# PrimaryBoard.net
KiCad netlist of a schematic drawn in EAGLE
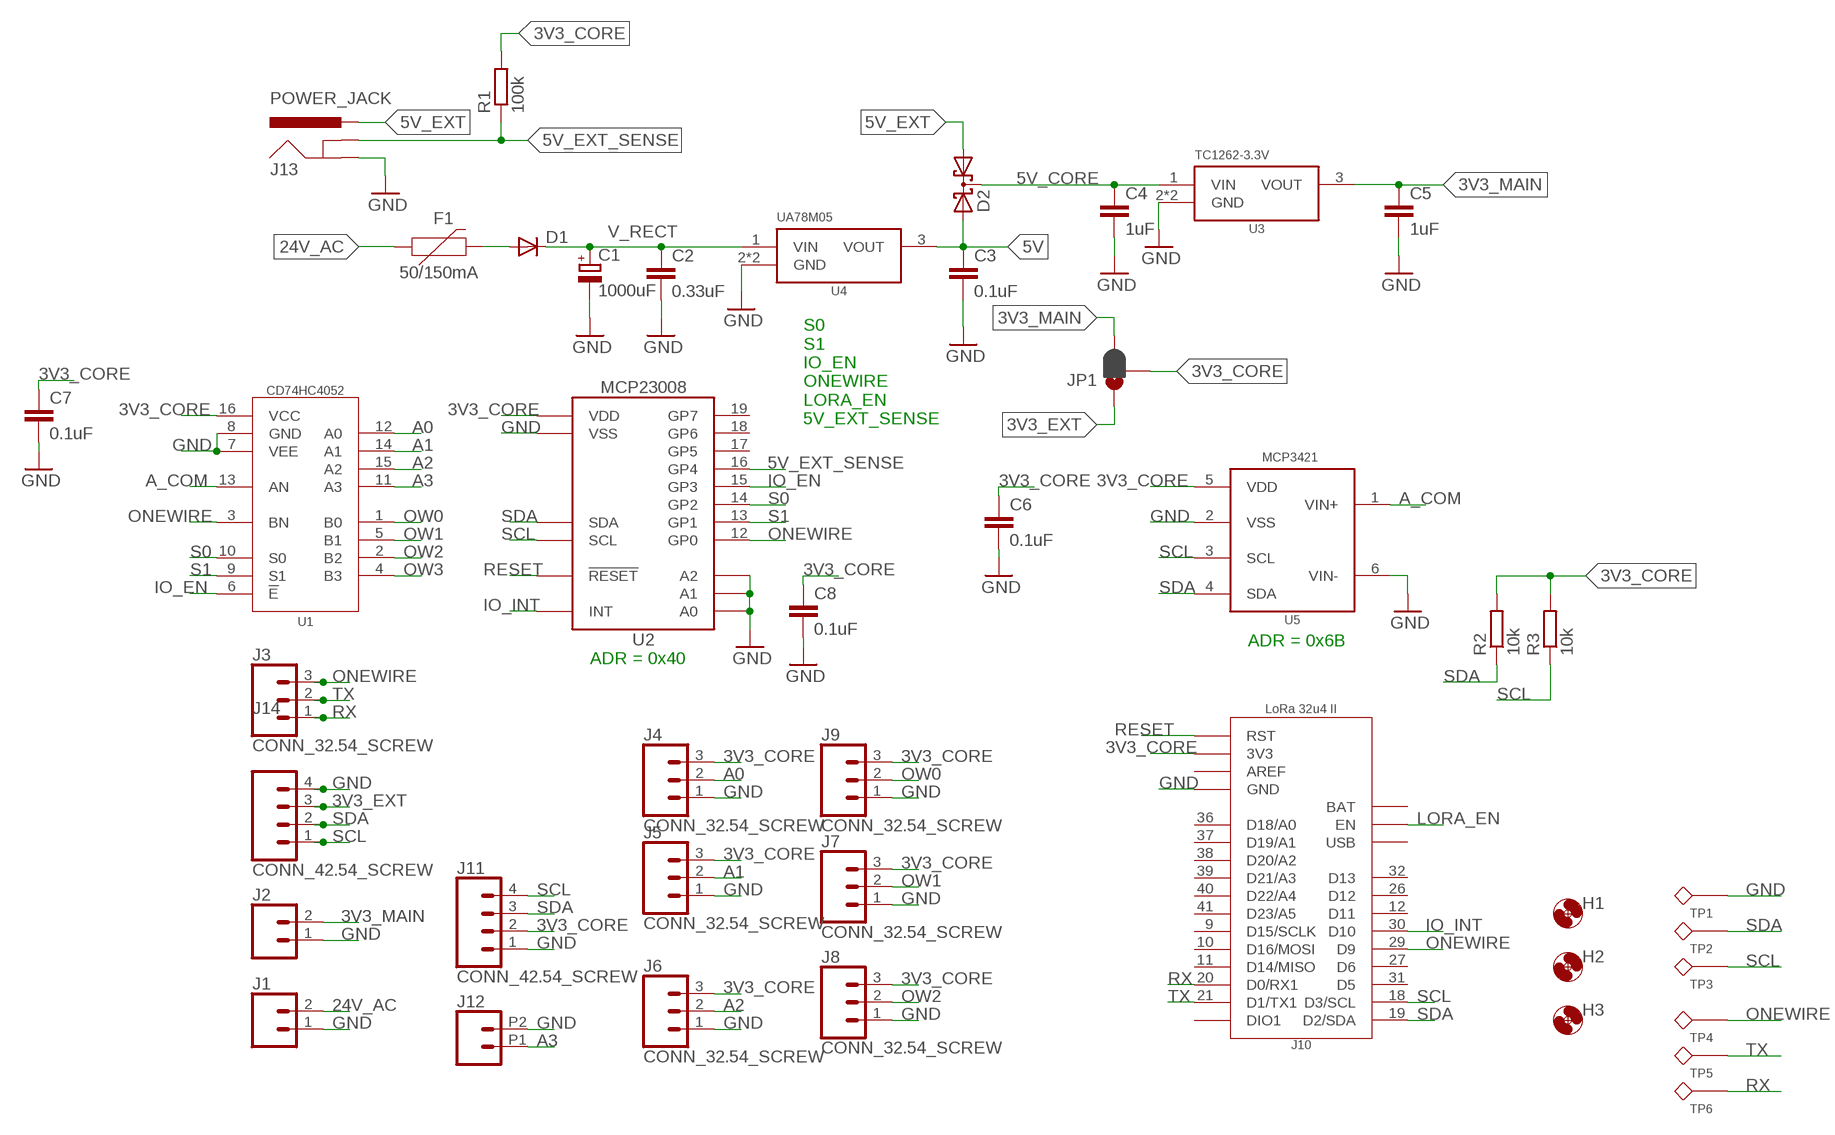
[diagram p0: schematic, sheet 1]

(export (version "E")
  (design (tool "Eeschema 10.0.6"))
  (components
    (comp (ref "C1")
      (value "1000uF")
      (footprint "eagle-import:PANASONIC_G")
      (fields (field (name "MF") "Panasonic") (field (name "MPN") "EEE-FT1E102UP"))
      (libsource (lib "eagle-import") (part "CPOL-EUG"))
    )
    (comp (ref "C2")
      (value "0.33uF")
      (footprint "eagle-import:C0805")
      (fields (field (name "MF") "Yageo") (field (name "MPN") "CC0805KKX7R9BB334"))
      (libsource (lib "eagle-import") (part "C-EUC08050.33UF"))
    )
    (comp (ref "C3")
      (value "0.1uF")
      (footprint "eagle-import:C0805")
      (fields (field (name "MF") "Kemet") (field (name "MPN") "C0805C104M3RACTU"))
      (libsource (lib "eagle-import") (part "C-EUC08050.1UF"))
    )
    (comp (ref "C4")
      (value "1uF")
      (footprint "eagle-import:C0805")
      (fields (field (name "MF") "Yageo") (field (name "MPN") "CC0805KKX7R8BB105"))
      (libsource (lib "eagle-import") (part "C-EUC08051UF"))
    )
    (comp (ref "C5")
      (value "1uF")
      (footprint "eagle-import:C0805")
      (fields (field (name "MF") "Yageo") (field (name "MPN") "CC0805KKX7R8BB105"))
      (libsource (lib "eagle-import") (part "C-EUC08051UF"))
    )
    (comp (ref "C6")
      (value "0.1uF")
      (footprint "eagle-import:C0805")
      (fields (field (name "MF") "Kemet") (field (name "MPN") "C0805C104M3RACTU"))
      (libsource (lib "eagle-import") (part "C-EUC08050.1UF"))
    )
    (comp (ref "C7")
      (value "0.1uF")
      (footprint "eagle-import:C0805")
      (fields (field (name "MF") "Kemet") (field (name "MPN") "C0805C104M3RACTU"))
      (libsource (lib "eagle-import") (part "C-EUC08050.1UF"))
    )
    (comp (ref "C8")
      (value "0.1uF")
      (footprint "eagle-import:C0805")
      (fields (field (name "MF") "Kemet") (field (name "MPN") "C0805C104M3RACTU"))
      (libsource (lib "eagle-import") (part "C-EUC08050.1UF"))
    )
    (comp (ref "D1")
      (value "DIODESOD-123")
      (footprint "eagle-import:SOD-123")
      (fields (field (name "MF") "Diodes Incorporated") (field (name "MPN") "1N5819HW-7-F"))
      (libsource (lib "eagle-import") (part "DIODESOD-123"))
    )
    (comp (ref "D2")
      (value "DIODE_CCSDM40E20LCSOT23")
      (footprint "eagle-import:SOT23-3")
      (fields (field (name "MF") "Diodes Incorporated") (field (name "MPN") "SDM40E20LC-7"))
      (libsource (lib "eagle-import") (part "DIODE_CCSOT23SDM40E20LC"))
    )
    (comp (ref "F1")
      (value "50/150mA")
      (footprint "eagle-import:1206")
      (fields (field (name "MF") "Bell Fuse") (field (name "MPN") "0ZCJ0005FF2E"))
      (libsource (lib "eagle-import") (part "PPTC1206150MA"))
    )
    (comp (ref "H1")
      (value "MOUNTING_HOLE2_NP")
      (footprint "eagle-import:2_56")
      (libsource (lib "eagle-import") (part "MOUNTING_HOLE2_NP"))
    )
    (comp (ref "H2")
      (value "MOUNTING_HOLE2_NP")
      (footprint "eagle-import:2_56")
      (libsource (lib "eagle-import") (part "MOUNTING_HOLE2_NP"))
    )
    (comp (ref "H3")
      (value "MOUNTING_HOLE2_NP")
      (footprint "eagle-import:2_56")
      (libsource (lib "eagle-import") (part "MOUNTING_HOLE2_NP"))
    )
    (comp (ref "J1")
      (value "CONN_0239532_RA")
      (footprint "eagle-import:1X02_39532_RIGHT")
      (fields (field (name "MF") "Molex") (field (name "MPN") "0395321002"))
      (libsource (lib "eagle-import") (part "CONN_0239532_RA"))
    )
    (comp (ref "J2")
      (value "CONN_023.5MM-NO_SILK")
      (footprint "eagle-import:SCREWTERMINAL-3.5MM-2-NS")
      (fields (field (name "MF") "On Shore Technology") (field (name "MPN") "OSTTE020161"))
      (libsource (lib "eagle-import") (part "CONN_023.5MM-NO_SILK"))
    )
    (comp (ref "J3")
      (value "CONN_32.54_SCREW")
      (footprint "eagle-import:1X03_SCREW")
      (fields (field (name "MF") "On Shore") (field (name "MPN") "OSTVN03A150"))
      (libsource (lib "eagle-import") (part "CONN_32.54_SCREW"))
    )
    (comp (ref "J4")
      (value "CONN_32.54_SCREW")
      (footprint "eagle-import:1X03_SCREW")
      (fields (field (name "MF") "On Shore") (field (name "MPN") "OSTVN03A150"))
      (libsource (lib "eagle-import") (part "CONN_32.54_SCREW"))
    )
    (comp (ref "J5")
      (value "CONN_32.54_SCREW")
      (footprint "eagle-import:1X03_SCREW")
      (fields (field (name "MF") "On Shore") (field (name "MPN") "OSTVN03A150"))
      (libsource (lib "eagle-import") (part "CONN_32.54_SCREW"))
    )
    (comp (ref "J6")
      (value "CONN_32.54_SCREW")
      (footprint "eagle-import:1X03_SCREW")
      (fields (field (name "MF") "On Shore") (field (name "MPN") "OSTVN03A150"))
      (libsource (lib "eagle-import") (part "CONN_32.54_SCREW"))
    )
    (comp (ref "J7")
      (value "CONN_32.54_SCREW")
      (footprint "eagle-import:1X03_SCREW")
      (fields (field (name "MF") "On Shore") (field (name "MPN") "OSTVN03A150"))
      (libsource (lib "eagle-import") (part "CONN_32.54_SCREW"))
    )
    (comp (ref "J8")
      (value "CONN_32.54_SCREW")
      (footprint "eagle-import:1X03_SCREW")
      (fields (field (name "MF") "On Shore") (field (name "MPN") "OSTVN03A150"))
      (libsource (lib "eagle-import") (part "CONN_32.54_SCREW"))
    )
    (comp (ref "J9")
      (value "CONN_32.54_SCREW")
      (footprint "eagle-import:1X03_SCREW")
      (fields (field (name "MF") "On Shore") (field (name "MPN") "OSTVN03A150"))
      (libsource (lib "eagle-import") (part "CONN_32.54_SCREW"))
    )
    (comp (ref "J10")
      (value "LORA32U4II")
      (footprint "eagle-import:LORA32U4II")
      (libsource (lib "eagle-import") (part "LORA32U4II"))
    )
    (comp (ref "J11")
      (value "CONN_42.54_SCREW")
      (footprint "eagle-import:1X04_SCREW")
      (fields (field (name "MF") "On Shore") (field (name "MPN") "OSTVN04A150"))
      (libsource (lib "eagle-import") (part "CONN_42.54_SCREW"))
    )
    (comp (ref "J12")
      (value "CONN_022.54_SCREW")
      (footprint "eagle-import:1X02_2.54_SCREWTERM")
      (fields (field (name "MF") "OnShore") (field (name "MPN") "OSTVN02A150"))
      (libsource (lib "eagle-import") (part "CONN_022.54_SCREW"))
    )
    (comp (ref "J13")
      (value "POWER_JACK")
      (footprint "eagle-import:POWER_JACK_PTH")
      (fields (field (name "MF") "CUI") (field (name "MPN") "PJ-202A"))
      (libsource (lib "eagle-import") (part "POWER_JACK"))
    )
    (comp (ref "J14")
      (value "CONN_42.54_SCREW")
      (footprint "eagle-import:1X04_SCREW")
      (fields (field (name "MF") "On Shore") (field (name "MPN") "OSTVN04A150"))
      (libsource (lib "eagle-import") (part "CONN_42.54_SCREW"))
    )
    (comp (ref "JP1")
      (value "JUMPER-SMT_3_1-NC_PASTE_SILK")
      (footprint "eagle-import:SMT-JUMPER_3_1-NC_PASTE_SILK")
      (libsource (lib "eagle-import") (part "JUMPER-SMT_3_1-NC_PASTE_SILK"))
    )
    (comp (ref "R1")
      (value "100k")
      (footprint "eagle-import:R0805")
      (fields (field (name "MF") "Yageo") (field (name "MPN") "RC0805FR-07100KL"))
      (libsource (lib "eagle-import") (part "R-EU_R0805100K"))
    )
    (comp (ref "R2")
      (value "10k")
      (footprint "eagle-import:R0805")
      (fields (field (name "MF") "Yageo") (field (name "MPN") "RC0805FR-0710KL"))
      (libsource (lib "eagle-import") (part "R-EU_R080510K"))
    )
    (comp (ref "R3")
      (value "10k")
      (footprint "eagle-import:R0805")
      (fields (field (name "MF") "Yageo") (field (name "MPN") "RC0805FR-0710KL"))
      (libsource (lib "eagle-import") (part "R-EU_R080510K"))
    )
    (comp (ref "TP1")
      (value "TESTPOINTRCU")
      (footprint "eagle-import:TESTPOINT_0603")
      (fields (field (name "MF") "TE Connectivity") (field (name "MPN") "RCU-0C"))
      (libsource (lib "eagle-import") (part "TESTPOINTRCU"))
    )
    (comp (ref "TP2")
      (value "TESTPOINTRCU")
      (footprint "eagle-import:TESTPOINT_0603")
      (fields (field (name "MF") "TE Connectivity") (field (name "MPN") "RCU-0C"))
      (libsource (lib "eagle-import") (part "TESTPOINTRCU"))
    )
    (comp (ref "TP3")
      (value "TESTPOINTRCU")
      (footprint "eagle-import:TESTPOINT_0603")
      (fields (field (name "MF") "TE Connectivity") (field (name "MPN") "RCU-0C"))
      (libsource (lib "eagle-import") (part "TESTPOINTRCU"))
    )
    (comp (ref "TP4")
      (value "TESTPOINTRCU")
      (footprint "eagle-import:TESTPOINT_0603")
      (fields (field (name "MF") "TE Connectivity") (field (name "MPN") "RCU-0C"))
      (libsource (lib "eagle-import") (part "TESTPOINTRCU"))
    )
    (comp (ref "TP5")
      (value "TESTPOINTRCU")
      (footprint "eagle-import:TESTPOINT_0603")
      (fields (field (name "MF") "TE Connectivity") (field (name "MPN") "RCU-0C"))
      (libsource (lib "eagle-import") (part "TESTPOINTRCU"))
    )
    (comp (ref "TP6")
      (value "TESTPOINTRCU")
      (footprint "eagle-import:TESTPOINT_0603")
      (fields (field (name "MF") "TE Connectivity") (field (name "MPN") "RCU-0C"))
      (libsource (lib "eagle-import") (part "TESTPOINTRCU"))
    )
    (comp (ref "U1")
      (value "CD74HC4052PW")
      (footprint "eagle-import:TSSOP16")
      (fields (field (name "MF") "TI") (field (name "MPN") "CD74HC4052PWR"))
      (libsource (lib "eagle-import") (part "CD74HC4052PW"))
    )
    (comp (ref "U2")
      (value "MCP23008SSOP")
      (footprint "eagle-import:SSOP20")
      (fields (field (name "MF") "Microchip") (field (name "MPN") "MCP23008T-E/SS"))
      (libsource (lib "eagle-import") (part "MCP23008SSOP"))
    )
    (comp (ref "U3")
      (value "TC1262-3.3V")
      (footprint "eagle-import:SOT223")
      (fields
        (field (name "DISP") "TC1262-3.3V")
        (field (name "MF") "Microchip")
        (field (name "MPN") "TC1262-3.3VDBTR")
      )
      (libsource (lib "eagle-import") (part "TC1262-3.3V"))
    )
    (comp (ref "U4")
      (value "UA78M05SOT223")
      (footprint "eagle-import:SOT223")
      (fields (field (name "DISP") "UA78M05") (field (name "MF") "TI") (field (name "MPN") "UA78M05IDCYR"))
      (libsource (lib "eagle-import") (part "UA78MSOT22305"))
    )
    (comp (ref "U5")
      (value "MCP3421A3")
      (footprint "eagle-import:SOT23-6L")
      (fields
        (field (name "DISP") "MCP3421")
        (field (name "MF") "Microchip")
        (field (name "MPN") "MCP3421A3T-E/CH")
      )
      (libsource (lib "eagle-import") (part "MCP3421A3"))
    )
  )
  (nets
    (net (code "1") (name "/5V_CORE") (class "Default")
      (node (ref "C4") (pin "1") (pinfunction "1_1") (pintype "passive"))
      (node (ref "D2") (pin "3") (pinfunction "C_3") (pintype "passive"))
      (node (ref "U3") (pin "1") (pinfunction "VIN_1") (pintype "power_in"))
    )
    (net (code "2") (name "/A0") (class "Default")
      (node (ref "J4") (pin "2") (pinfunction "2_2") (pintype "passive"))
      (node (ref "U1") (pin "12") (pinfunction "A0_12") (pintype "bidirectional"))
    )
    (net (code "3") (name "/A1") (class "Default")
      (node (ref "J5") (pin "2") (pinfunction "2_2") (pintype "passive"))
      (node (ref "U1") (pin "14") (pinfunction "A1_14") (pintype "bidirectional"))
    )
    (net (code "4") (name "/A2") (class "Default")
      (node (ref "J6") (pin "2") (pinfunction "2_2") (pintype "passive"))
      (node (ref "U1") (pin "15") (pinfunction "A2_15") (pintype "bidirectional"))
    )
    (net (code "5") (name "/A3") (class "Default")
      (node (ref "J12") (pin "P1") (pinfunction "1_P1") (pintype "passive"))
      (node (ref "U1") (pin "11") (pinfunction "A3_11") (pintype "bidirectional"))
    )
    (net (code "6") (name "/A_COM") (class "Default")
      (node (ref "U1") (pin "13") (pinfunction "AN_13") (pintype "bidirectional"))
      (node (ref "U5") (pin "1") (pinfunction "VIN+_1") (pintype "input"))
    )
    (net (code "7") (name "/BAT") (class "Default")
      (node (ref "J10") (pin "BAT") (pinfunction "BAT_BAT") (pintype "power_in"))
    )
    (net (code "8") (name "/IO_EN") (class "Default")
      (node (ref "U1") (pin "6") (pinfunction "~{E}_6") (pintype "input"))
      (node (ref "U2") (pin "15") (pinfunction "GP3_15") (pintype "bidirectional"))
    )
    (net (code "9") (name "/IO_INT") (class "Default")
      (node (ref "J10") (pin "30") (pinfunction "D10_30") (pintype "bidirectional"))
      (node (ref "U2") (pin "8") (pinfunction "INT_8") (pintype "output"))
    )
    (net (code "10") (name "/LORA_EN") (class "Default")
      (node (ref "J10") (pin "EN") (pinfunction "EN_EN") (pintype "input"))
    )
    (net (code "11") (name "/ONEWIRE") (class "Default")
      (node (ref "J10") (pin "29") (pinfunction "D9_29") (pintype "bidirectional"))
      (node (ref "J3") (pin "3") (pinfunction "3_3") (pintype "passive"))
      (node (ref "TP4") (pin "1") (pinfunction "P$1_1") (pintype "bidirectional"))
      (node (ref "U1") (pin "3") (pinfunction "BN_3") (pintype "bidirectional"))
      (node (ref "U2") (pin "12") (pinfunction "GP0_12") (pintype "bidirectional"))
    )
    (net (code "12") (name "/OW0") (class "Default")
      (node (ref "J9") (pin "2") (pinfunction "2_2") (pintype "passive"))
      (node (ref "U1") (pin "1") (pinfunction "B0_1") (pintype "bidirectional"))
    )
    (net (code "13") (name "/OW1") (class "Default")
      (node (ref "J7") (pin "2") (pinfunction "2_2") (pintype "passive"))
      (node (ref "U1") (pin "5") (pinfunction "B1_5") (pintype "bidirectional"))
    )
    (net (code "14") (name "/OW2") (class "Default")
      (node (ref "J8") (pin "2") (pinfunction "2_2") (pintype "passive"))
      (node (ref "U1") (pin "2") (pinfunction "B2_2") (pintype "bidirectional"))
    )
    (net (code "15") (name "/OW3") (class "Default")
      (node (ref "U1") (pin "4") (pinfunction "B3_4") (pintype "bidirectional"))
    )
    (net (code "16") (name "/RESET") (class "Default")
      (node (ref "J10") (pin "RST") (pinfunction "RST_RST") (pintype "input"))
      (node (ref "U2") (pin "6") (pinfunction "~{RESET}_6") (pintype "input"))
    )
    (net (code "17") (name "/RX") (class "Default")
      (node (ref "J10") (pin "20") (pinfunction "D0/RX1_20") (pintype "bidirectional"))
      (node (ref "J3") (pin "1") (pinfunction "1_1") (pintype "passive"))
      (node (ref "TP6") (pin "1") (pinfunction "P$1_1") (pintype "bidirectional"))
    )
    (net (code "18") (name "/S0") (class "Default")
      (node (ref "U1") (pin "10") (pinfunction "S0_10") (pintype "input"))
      (node (ref "U2") (pin "14") (pinfunction "GP2_14") (pintype "bidirectional"))
    )
    (net (code "19") (name "/S1") (class "Default")
      (node (ref "U1") (pin "9") (pinfunction "S1_9") (pintype "input"))
      (node (ref "U2") (pin "13") (pinfunction "GP1_13") (pintype "bidirectional"))
    )
    (net (code "20") (name "/SCL") (class "Default")
      (node (ref "J10") (pin "18") (pinfunction "D3/SCL_18") (pintype "bidirectional"))
      (node (ref "J11") (pin "4") (pinfunction "4_4") (pintype "passive"))
      (node (ref "J14") (pin "1") (pinfunction "1_1") (pintype "passive"))
      (node (ref "R3") (pin "1") (pinfunction "1_1") (pintype "passive"))
      (node (ref "TP3") (pin "1") (pinfunction "P$1_1") (pintype "bidirectional"))
      (node (ref "U2") (pin "1") (pinfunction "SCL_1") (pintype "input"))
      (node (ref "U5") (pin "3") (pinfunction "SCL_3") (pintype "bidirectional"))
    )
    (net (code "21") (name "/SDA") (class "Default")
      (node (ref "J10") (pin "19") (pinfunction "D2/SDA_19") (pintype "bidirectional"))
      (node (ref "J11") (pin "3") (pinfunction "3_3") (pintype "passive"))
      (node (ref "J14") (pin "2") (pinfunction "2_2") (pintype "passive"))
      (node (ref "R2") (pin "1") (pinfunction "1_1") (pintype "passive"))
      (node (ref "TP2") (pin "1") (pinfunction "P$1_1") (pintype "bidirectional"))
      (node (ref "U2") (pin "2") (pinfunction "SDA_2") (pintype "bidirectional"))
      (node (ref "U5") (pin "4") (pinfunction "SDA_4") (pintype "bidirectional"))
    )
    (net (code "22") (name "/TX") (class "Default")
      (node (ref "J10") (pin "21") (pinfunction "D1/TX1_21") (pintype "bidirectional"))
      (node (ref "J3") (pin "2") (pinfunction "2_2") (pintype "passive"))
      (node (ref "TP5") (pin "1") (pinfunction "P$1_1") (pintype "bidirectional"))
    )
    (net (code "23") (name "/USB") (class "Default")
      (node (ref "J10") (pin "USB") (pinfunction "USB_USB") (pintype "power_in"))
    )
    (net (code "24") (name "/V_RECT") (class "Default")
      (node (ref "C1") (pin "+") (pinfunction "+_+") (pintype "passive"))
      (node (ref "C2") (pin "1") (pinfunction "1_1") (pintype "passive"))
      (node (ref "D1") (pin "CAT") (pinfunction "C_CAT") (pintype "passive"))
      (node (ref "U4") (pin "1") (pinfunction "VIN_1") (pintype "power_in"))
    )
    (net (code "25") (name "3V3_CORE") (class "Default")
      (node (ref "C6") (pin "1") (pinfunction "1_1") (pintype "passive"))
      (node (ref "C7") (pin "1") (pinfunction "1_1") (pintype "passive"))
      (node (ref "C8") (pin "1") (pinfunction "1_1") (pintype "passive"))
      (node (ref "J10") (pin "3V3") (pinfunction "3V3_3V3") (pintype "power_in"))
      (node (ref "J11") (pin "2") (pinfunction "2_2") (pintype "passive"))
      (node (ref "J4") (pin "3") (pinfunction "3_3") (pintype "passive"))
      (node (ref "J5") (pin "3") (pinfunction "3_3") (pintype "passive"))
      (node (ref "J6") (pin "3") (pinfunction "3_3") (pintype "passive"))
      (node (ref "J7") (pin "3") (pinfunction "3_3") (pintype "passive"))
      (node (ref "J8") (pin "3") (pinfunction "3_3") (pintype "passive"))
      (node (ref "J9") (pin "3") (pinfunction "3_3") (pintype "passive"))
      (node (ref "JP1") (pin "2") (pinfunction "2_2") (pintype "passive"))
      (node (ref "R1") (pin "2") (pinfunction "2_2") (pintype "passive"))
      (node (ref "R2") (pin "2") (pinfunction "2_2") (pintype "passive"))
      (node (ref "R3") (pin "2") (pinfunction "2_2") (pintype "passive"))
      (node (ref "U1") (pin "16") (pinfunction "VCC_16") (pintype "power_in"))
      (node (ref "U2") (pin "20") (pinfunction "VDD_20") (pintype "power_in"))
      (node (ref "U5") (pin "5") (pinfunction "VDD_5") (pintype "passive"))
    )
    (net (code "26") (name "3V3_EXT") (class "Default")
      (node (ref "J14") (pin "3") (pinfunction "3_3") (pintype "passive"))
      (node (ref "JP1") (pin "1") (pinfunction "1_1") (pintype "passive"))
    )
    (net (code "27") (name "3V3_MAIN") (class "Default")
      (node (ref "C5") (pin "1") (pinfunction "1_1") (pintype "passive"))
      (node (ref "J2") (pin "2") (pinfunction "2_2") (pintype "passive"))
      (node (ref "JP1") (pin "3") (pinfunction "3_3") (pintype "passive"))
      (node (ref "U3") (pin "3") (pinfunction "VOUT_3") (pintype "power_in"))
    )
    (net (code "28") (name "5V") (class "Default")
      (node (ref "C3") (pin "1") (pinfunction "1_1") (pintype "passive"))
      (node (ref "D2") (pin "2") (pinfunction "A2_2") (pintype "passive"))
      (node (ref "U4") (pin "3") (pinfunction "VOUT_3") (pintype "power_in"))
    )
    (net (code "29") (name "5V_EXT") (class "Default")
      (node (ref "D2") (pin "1") (pinfunction "A1_1") (pintype "passive"))
      (node (ref "J13") (pin "PWR") (pinfunction "PWR_PWR") (pintype "bidirectional"))
    )
    (net (code "30") (name "5V_EXT_SENSE") (class "Default")
      (node (ref "J13") (pin "GNDBREAK") (pinfunction "GNDBREAK_GNDBREAK") (pintype "bidirectional"))
      (node (ref "R1") (pin "1") (pinfunction "1_1") (pintype "passive"))
      (node (ref "U2") (pin "16") (pinfunction "GP4_16") (pintype "bidirectional"))
    )
    (net (code "31") (name "24V_AC") (class "Default")
      (node (ref "F1") (pin "1") (pinfunction "1_1") (pintype "bidirectional"))
      (node (ref "J1") (pin "2") (pinfunction "2_2") (pintype "passive"))
    )
    (net (code "32") (name "GND") (class "Default")
      (node (ref "C1") (pin "-") (pinfunction "-_-") (pintype "passive"))
      (node (ref "C2") (pin "2") (pinfunction "2_2") (pintype "passive"))
      (node (ref "C3") (pin "2") (pinfunction "2_2") (pintype "passive"))
      (node (ref "C4") (pin "2") (pinfunction "2_2") (pintype "passive"))
      (node (ref "C5") (pin "2") (pinfunction "2_2") (pintype "passive"))
      (node (ref "C6") (pin "2") (pinfunction "2_2") (pintype "passive"))
      (node (ref "C7") (pin "2") (pinfunction "2_2") (pintype "passive"))
      (node (ref "C8") (pin "2") (pinfunction "2_2") (pintype "passive"))
      (node (ref "J1") (pin "1") (pinfunction "1_1") (pintype "passive"))
      (node (ref "J10") (pin "GND") (pinfunction "GND_GND") (pintype "power_in"))
      (node (ref "J11") (pin "1") (pinfunction "1_1") (pintype "passive"))
      (node (ref "J12") (pin "P2") (pinfunction "2_P2") (pintype "passive"))
      (node (ref "J13") (pin "GND") (pinfunction "GND_GND") (pintype "bidirectional"))
      (node (ref "J14") (pin "4") (pinfunction "4_4") (pintype "passive"))
      (node (ref "J2") (pin "1") (pinfunction "1_1") (pintype "passive"))
      (node (ref "J4") (pin "1") (pinfunction "1_1") (pintype "passive"))
      (node (ref "J5") (pin "1") (pinfunction "1_1") (pintype "passive"))
      (node (ref "J6") (pin "1") (pinfunction "1_1") (pintype "passive"))
      (node (ref "J7") (pin "1") (pinfunction "1_1") (pintype "passive"))
      (node (ref "J8") (pin "1") (pinfunction "1_1") (pintype "passive"))
      (node (ref "J9") (pin "1") (pinfunction "1_1") (pintype "passive"))
      (node (ref "TP1") (pin "1") (pinfunction "P$1_1") (pintype "bidirectional"))
      (node (ref "U1") (pin "7") (pinfunction "VEE_7") (pintype "power_in"))
      (node (ref "U1") (pin "8") (pinfunction "GND_8") (pintype "power_in"))
      (node (ref "U2") (pin "3") (pinfunction "A2_3") (pintype "input"))
      (node (ref "U2") (pin "4") (pinfunction "A1_4") (pintype "input"))
      (node (ref "U2") (pin "5") (pinfunction "A0_5") (pintype "input"))
      (node (ref "U2") (pin "9") (pinfunction "VSS_9") (pintype "power_in"))
      (node (ref "U3") (pin "2") (pinfunction "GND_2") (pintype "power_in"))
      (node (ref "U3") (pin "4") (pinfunction "GND_4") (pintype "power_in"))
      (node (ref "U4") (pin "2") (pinfunction "GND_2") (pintype "power_in"))
      (node (ref "U4") (pin "4") (pinfunction "GND_4") (pintype "power_in"))
      (node (ref "U5") (pin "2") (pinfunction "VSS_2") (pintype "passive"))
      (node (ref "U5") (pin "6") (pinfunction "VIN-_6") (pintype "input"))
    )
    (net (code "33") (name "Net-(D1-A)") (class "Default")
      (node (ref "D1") (pin "ANODE") (pinfunction "A_ANODE") (pintype "passive"))
      (node (ref "F1") (pin "2") (pinfunction "2_2") (pintype "bidirectional"))
    )
    (net (code "34") (name "unconnected-(J10-D5-Pad31)") (class "Default")
      (node (ref "J10") (pin "31") (pinfunction "D5_31") (pintype "bidirectional"))
    )
    (net (code "35") (name "unconnected-(J10-D6-Pad27)") (class "Default")
      (node (ref "J10") (pin "27") (pinfunction "D6_27") (pintype "bidirectional"))
    )
    (net (code "36") (name "unconnected-(J10-D11-Pad12)") (class "Default")
      (node (ref "J10") (pin "12") (pinfunction "D11_12") (pintype "bidirectional"))
    )
    (net (code "37") (name "unconnected-(J10-D12-Pad26)") (class "Default")
      (node (ref "J10") (pin "26") (pinfunction "D12_26") (pintype "bidirectional"))
    )
    (net (code "38") (name "unconnected-(J10-D13-Pad32)") (class "Default")
      (node (ref "J10") (pin "32") (pinfunction "D13_32") (pintype "bidirectional"))
    )
    (net (code "39") (name "unconnected-(J10-D14{slash}MISO-Pad11)") (class "Default")
      (node (ref "J10") (pin "11") (pinfunction "D14/MISO_11") (pintype "bidirectional"))
    )
    (net (code "40") (name "unconnected-(J10-D15{slash}SCLK-Pad9)") (class "Default")
      (node (ref "J10") (pin "9") (pinfunction "D15/SCLK_9") (pintype "bidirectional"))
    )
    (net (code "41") (name "unconnected-(J10-D16{slash}MOSI-Pad10)") (class "Default")
      (node (ref "J10") (pin "10") (pinfunction "D16/MOSI_10") (pintype "bidirectional"))
    )
    (net (code "42") (name "unconnected-(J10-D18{slash}A0-Pad36)") (class "Default")
      (node (ref "J10") (pin "36") (pinfunction "D18/A0_36") (pintype "bidirectional"))
    )
    (net (code "43") (name "unconnected-(J10-D19{slash}A1-Pad37)") (class "Default")
      (node (ref "J10") (pin "37") (pinfunction "D19/A1_37") (pintype "bidirectional"))
    )
    (net (code "44") (name "unconnected-(J10-D20{slash}A2-Pad38)") (class "Default")
      (node (ref "J10") (pin "38") (pinfunction "D20/A2_38") (pintype "bidirectional"))
    )
    (net (code "45") (name "unconnected-(J10-D21{slash}A3-Pad39)") (class "Default")
      (node (ref "J10") (pin "39") (pinfunction "D21/A3_39") (pintype "bidirectional"))
    )
    (net (code "46") (name "unconnected-(J10-D22{slash}A4-Pad40)") (class "Default")
      (node (ref "J10") (pin "40") (pinfunction "D22/A4_40") (pintype "bidirectional"))
    )
    (net (code "47") (name "unconnected-(J10-D23{slash}A5-Pad41)") (class "Default")
      (node (ref "J10") (pin "41") (pinfunction "D23/A5_41") (pintype "bidirectional"))
    )
    (net (code "48") (name "unconnected-(J10-PadAREF)") (class "Default")
      (node (ref "J10") (pin "AREF") (pinfunction "AREF_AREF") (pintype "input"))
    )
    (net (code "49") (name "unconnected-(J10-PadDIO1)") (class "Default")
      (node (ref "J10") (pin "DIO1") (pinfunction "DIO1_DIO1") (pintype "bidirectional"))
    )
    (net (code "50") (name "unconnected-(U2-GP5-Pad17)") (class "Default")
      (node (ref "U2") (pin "17") (pinfunction "GP5_17") (pintype "bidirectional"))
    )
    (net (code "51") (name "unconnected-(U2-GP6-Pad18)") (class "Default")
      (node (ref "U2") (pin "18") (pinfunction "GP6_18") (pintype "bidirectional"))
    )
    (net (code "52") (name "unconnected-(U2-GP7-Pad19)") (class "Default")
      (node (ref "U2") (pin "19") (pinfunction "GP7_19") (pintype "bidirectional"))
    )
  )
)
